# as14120_fpga_ddr_cypress.net
KiCad netlist of a schematic drawn in Altium Designer
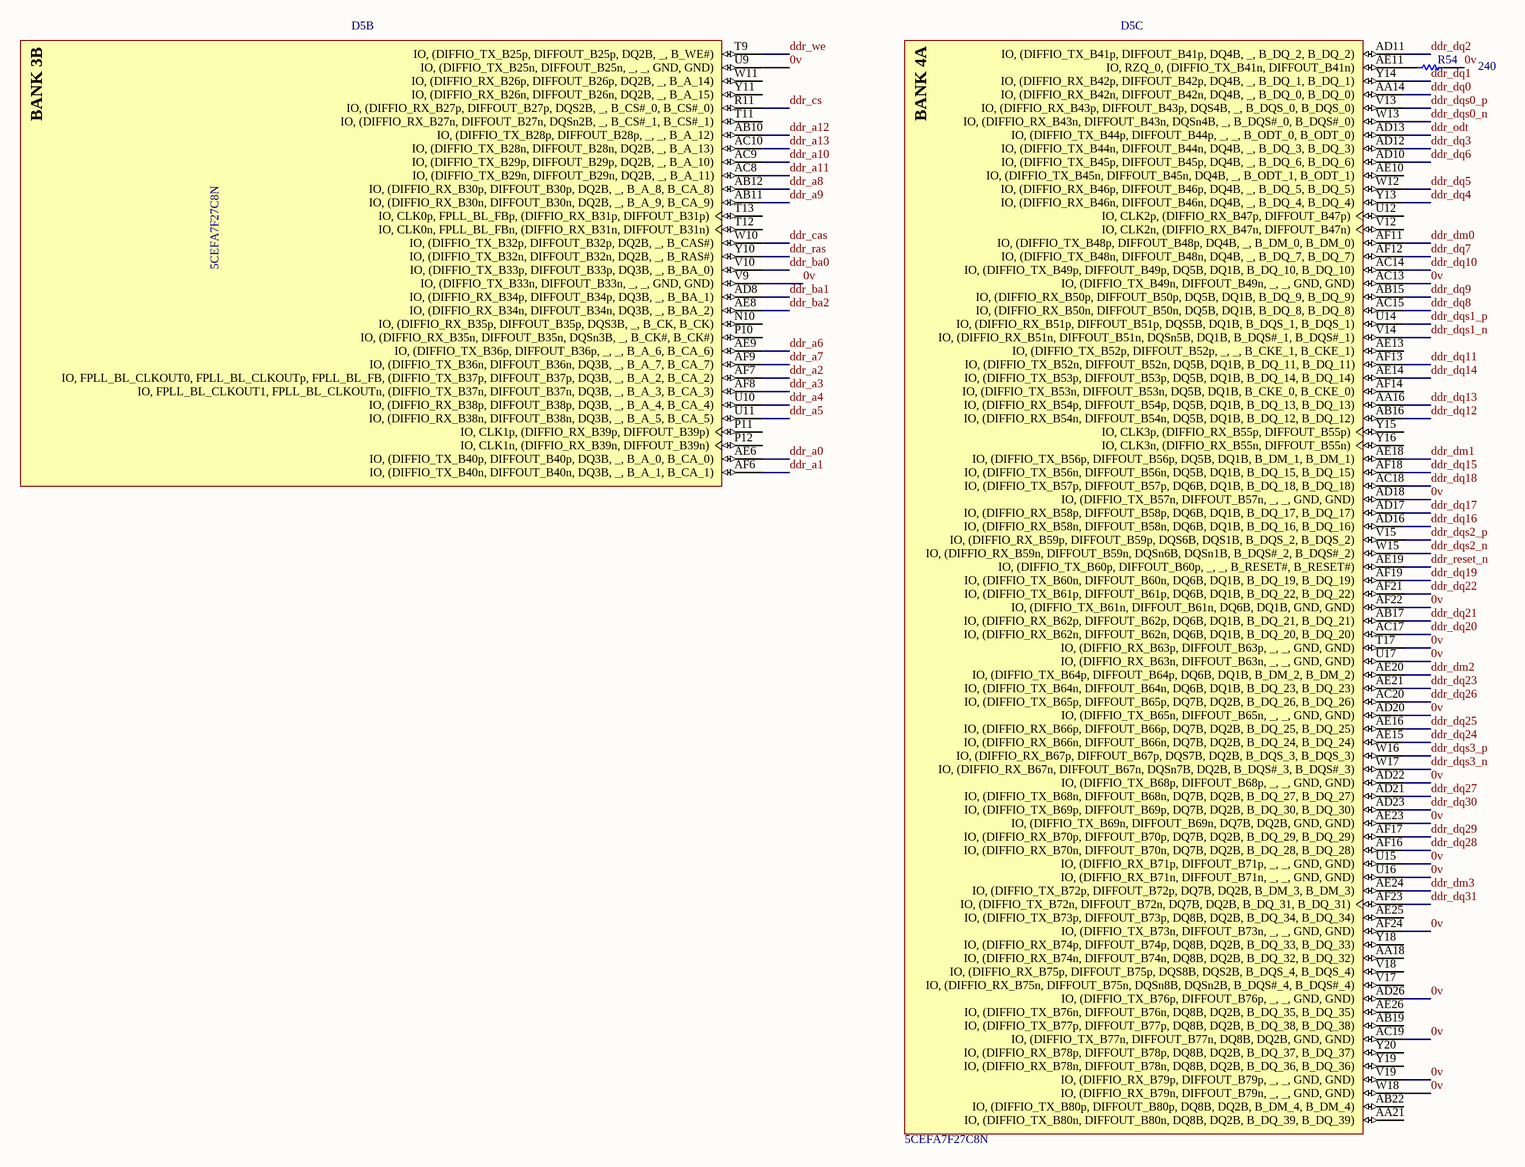
[diagram p0: as14120_fpga_ddr_cypress.SchDoc]

(export (version "E")
  (design (tool "Eeschema 10.0.6"))
  (components
    (comp (ref "D5")
      (value "5CEFA7F27C8N")
      (footprint "ALTR-672-FBGA-2000A")
      (fields (field (name "MANUFACTURER") "Altera"))
      (libsource (lib "Altera Cyclone V E") (part "5CEFA7F27C8N"))
    )
    (comp (ref "R54")
      (value "240")
      (footprint "RESC0805(2012)_L")
      (description "1K 0.125W 1% 0805 (2012 Metric)  SMD")
      (fields (field (name "TOLERANCE") "1 %") (field (name "POWER") "0.125 W"))
      (libsource (lib "as14120") (part "RES_0805"))
    )
  )
  (nets
    (net (code "1") (name "/0v") (class "Default")
      (node (ref "D5") (pin "AC13") (pinfunction "IO,_(DIFFIO_TX_B49n,_DIFFOUT_B49n,__,__,_GND,_GND)_AC13") (pintype "bidirectional"))
      (node (ref "D5") (pin "AC19") (pinfunction "IO,_(DIFFIO_TX_B77n,_DIFFOUT_B77n,_DQ8B,_DQ2B,_GND,_GND)_AC19") (pintype "bidirectional"))
      (node (ref "D5") (pin "AD18") (pinfunction "IO,_(DIFFIO_TX_B57n,_DIFFOUT_B57n,__,__,_GND,_GND)_AD18") (pintype "bidirectional"))
      (node (ref "D5") (pin "AD20") (pinfunction "IO,_(DIFFIO_TX_B65n,_DIFFOUT_B65n,__,__,_GND,_GND)_AD20") (pintype "bidirectional"))
      (node (ref "D5") (pin "AD22") (pinfunction "IO,_(DIFFIO_TX_B68p,_DIFFOUT_B68p,__,__,_GND,_GND)_AD22") (pintype "bidirectional"))
      (node (ref "D5") (pin "AD26") (pinfunction "IO,_(DIFFIO_TX_B76p,_DIFFOUT_B76p,__,__,_GND,_GND)_AD26") (pintype "bidirectional"))
      (node (ref "D5") (pin "AE23") (pinfunction "IO,_(DIFFIO_TX_B69n,_DIFFOUT_B69n,_DQ7B,_DQ2B,_GND,_GND)_AE23") (pintype "bidirectional"))
      (node (ref "D5") (pin "AF22") (pinfunction "IO,_(DIFFIO_TX_B61n,_DIFFOUT_B61n,_DQ6B,_DQ1B,_GND,_GND)_AF22") (pintype "bidirectional"))
      (node (ref "D5") (pin "AF24") (pinfunction "IO,_(DIFFIO_TX_B73n,_DIFFOUT_B73n,__,__,_GND,_GND)_AF24") (pintype "bidirectional"))
      (node (ref "D5") (pin "T17") (pinfunction "IO,_(DIFFIO_RX_B63p,_DIFFOUT_B63p,__,__,_GND,_GND)_T17") (pintype "bidirectional"))
      (node (ref "D5") (pin "U15") (pinfunction "IO,_(DIFFIO_RX_B71p,_DIFFOUT_B71p,__,__,_GND,_GND)_U15") (pintype "bidirectional"))
      (node (ref "D5") (pin "U16") (pinfunction "IO,_(DIFFIO_RX_B71n,_DIFFOUT_B71n,__,__,_GND,_GND)_U16") (pintype "bidirectional"))
      (node (ref "D5") (pin "U17") (pinfunction "IO,_(DIFFIO_RX_B63n,_DIFFOUT_B63n,__,__,_GND,_GND)_U17") (pintype "bidirectional"))
      (node (ref "D5") (pin "U9") (pinfunction "IO,_(DIFFIO_TX_B25n,_DIFFOUT_B25n,__,__,_GND,_GND)_U9") (pintype "bidirectional"))
      (node (ref "D5") (pin "V19") (pinfunction "IO,_(DIFFIO_RX_B79p,_DIFFOUT_B79p,__,__,_GND,_GND)_V19") (pintype "bidirectional"))
      (node (ref "D5") (pin "V9") (pinfunction "IO,_(DIFFIO_TX_B33n,_DIFFOUT_B33n,__,__,_GND,_GND)_V9") (pintype "bidirectional"))
      (node (ref "D5") (pin "W18") (pinfunction "IO,_(DIFFIO_RX_B79n,_DIFFOUT_B79n,__,__,_GND,_GND)_W18") (pintype "bidirectional"))
      (node (ref "R54") (pin "2") (pinfunction "2_2") (pintype "passive"))
    )
    (net (code "2") (name "/ddr_a0") (class "Default")
      (node (ref "D5") (pin "AE6") (pinfunction "IO,_(DIFFIO_TX_B40p,_DIFFOUT_B40p,_DQ3B,__,_B_A_0,_B_CA_0)_AE6") (pintype "bidirectional"))
    )
    (net (code "3") (name "/ddr_a1") (class "Default")
      (node (ref "D5") (pin "AF6") (pinfunction "IO,_(DIFFIO_TX_B40n,_DIFFOUT_B40n,_DQ3B,__,_B_A_1,_B_CA_1)_AF6") (pintype "bidirectional"))
    )
    (net (code "4") (name "/ddr_a2") (class "Default")
      (node (ref "D5") (pin "AF7") (pinfunction "IO,_FPLL_BL_CLKOUT0,_FPLL_BL_CLKOUTp,_FPLL_BL_FB,_(DIFFIO_TX_B37p,_DIFFOUT_B37p,_DQ3B,__,_B_A_2,_B_CA_2)_AF7") (pintype "bidirectional"))
    )
    (net (code "5") (name "/ddr_a3") (class "Default")
      (node (ref "D5") (pin "AF8") (pinfunction "IO,_FPLL_BL_CLKOUT1,_FPLL_BL_CLKOUTn,_(DIFFIO_TX_B37n,_DIFFOUT_B37n,_DQ3B,__,_B_A_3,_B_CA_3)_AF8") (pintype "bidirectional"))
    )
    (net (code "6") (name "/ddr_a4") (class "Default")
      (node (ref "D5") (pin "U10") (pinfunction "IO,_(DIFFIO_RX_B38p,_DIFFOUT_B38p,_DQ3B,__,_B_A_4,_B_CA_4)_U10") (pintype "bidirectional"))
    )
    (net (code "7") (name "/ddr_a5") (class "Default")
      (node (ref "D5") (pin "U11") (pinfunction "IO,_(DIFFIO_RX_B38n,_DIFFOUT_B38n,_DQ3B,__,_B_A_5,_B_CA_5)_U11") (pintype "bidirectional"))
    )
    (net (code "8") (name "/ddr_a6") (class "Default")
      (node (ref "D5") (pin "AE9") (pinfunction "IO,_(DIFFIO_TX_B36p,_DIFFOUT_B36p,__,__,_B_A_6,_B_CA_6)_AE9") (pintype "bidirectional"))
    )
    (net (code "9") (name "/ddr_a7") (class "Default")
      (node (ref "D5") (pin "AF9") (pinfunction "IO,_(DIFFIO_TX_B36n,_DIFFOUT_B36n,_DQ3B,__,_B_A_7,_B_CA_7)_AF9") (pintype "bidirectional"))
    )
    (net (code "10") (name "/ddr_a8") (class "Default")
      (node (ref "D5") (pin "AB12") (pinfunction "IO,_(DIFFIO_RX_B30p,_DIFFOUT_B30p,_DQ2B,__,_B_A_8,_B_CA_8)_AB12") (pintype "bidirectional"))
    )
    (net (code "11") (name "/ddr_a9") (class "Default")
      (node (ref "D5") (pin "AB11") (pinfunction "IO,_(DIFFIO_RX_B30n,_DIFFOUT_B30n,_DQ2B,__,_B_A_9,_B_CA_9)_AB11") (pintype "bidirectional"))
    )
    (net (code "12") (name "/ddr_a10") (class "Default")
      (node (ref "D5") (pin "AC9") (pinfunction "IO,_(DIFFIO_TX_B29p,_DIFFOUT_B29p,_DQ2B,__,_B_A_10)_AC9") (pintype "bidirectional"))
    )
    (net (code "13") (name "/ddr_a11") (class "Default")
      (node (ref "D5") (pin "AC8") (pinfunction "IO,_(DIFFIO_TX_B29n,_DIFFOUT_B29n,_DQ2B,__,_B_A_11)_AC8") (pintype "bidirectional"))
    )
    (net (code "14") (name "/ddr_a12") (class "Default")
      (node (ref "D5") (pin "AB10") (pinfunction "IO,_(DIFFIO_TX_B28p,_DIFFOUT_B28p,__,__,_B_A_12)_AB10") (pintype "bidirectional"))
    )
    (net (code "15") (name "/ddr_a13") (class "Default")
      (node (ref "D5") (pin "AC10") (pinfunction "IO,_(DIFFIO_TX_B28n,_DIFFOUT_B28n,_DQ2B,__,_B_A_13)_AC10") (pintype "bidirectional"))
    )
    (net (code "16") (name "/ddr_ba0") (class "Default")
      (node (ref "D5") (pin "V10") (pinfunction "IO,_(DIFFIO_TX_B33p,_DIFFOUT_B33p,_DQ3B,__,_B_BA_0)_V10") (pintype "bidirectional"))
    )
    (net (code "17") (name "/ddr_ba1") (class "Default")
      (node (ref "D5") (pin "AD8") (pinfunction "IO,_(DIFFIO_RX_B34p,_DIFFOUT_B34p,_DQ3B,__,_B_BA_1)_AD8") (pintype "bidirectional"))
    )
    (net (code "18") (name "/ddr_ba2") (class "Default")
      (node (ref "D5") (pin "AE8") (pinfunction "IO,_(DIFFIO_RX_B34n,_DIFFOUT_B34n,_DQ3B,__,_B_BA_2)_AE8") (pintype "bidirectional"))
    )
    (net (code "19") (name "/ddr_cas") (class "Default")
      (node (ref "D5") (pin "W10") (pinfunction "IO,_(DIFFIO_TX_B32p,_DIFFOUT_B32p,_DQ2B,__,_B_CAS#)_W10") (pintype "bidirectional"))
    )
    (net (code "20") (name "/ddr_cs") (class "Default")
      (node (ref "D5") (pin "R11") (pinfunction "IO,_(DIFFIO_RX_B27p,_DIFFOUT_B27p,_DQS2B,__,_B_CS#_0,_B_CS#_0)_R11") (pintype "bidirectional"))
    )
    (net (code "21") (name "/ddr_dm0") (class "Default")
      (node (ref "D5") (pin "AF11") (pinfunction "IO,_(DIFFIO_TX_B48p,_DIFFOUT_B48p,_DQ4B,__,_B_DM_0,_B_DM_0)_AF11") (pintype "bidirectional"))
    )
    (net (code "22") (name "/ddr_dm1") (class "Default")
      (node (ref "D5") (pin "AE18") (pinfunction "IO,_(DIFFIO_TX_B56p,_DIFFOUT_B56p,_DQ5B,_DQ1B,_B_DM_1,_B_DM_1)_AE18") (pintype "bidirectional"))
    )
    (net (code "23") (name "/ddr_dm2") (class "Default")
      (node (ref "D5") (pin "AE20") (pinfunction "IO,_(DIFFIO_TX_B64p,_DIFFOUT_B64p,_DQ6B,_DQ1B,_B_DM_2,_B_DM_2)_AE20") (pintype "bidirectional"))
    )
    (net (code "24") (name "/ddr_dm3") (class "Default")
      (node (ref "D5") (pin "AE24") (pinfunction "IO,_(DIFFIO_TX_B72p,_DIFFOUT_B72p,_DQ7B,_DQ2B,_B_DM_3,_B_DM_3)_AE24") (pintype "bidirectional"))
    )
    (net (code "25") (name "/ddr_dq0") (class "Default")
      (node (ref "D5") (pin "AA14") (pinfunction "IO,_(DIFFIO_RX_B42n,_DIFFOUT_B42n,_DQ4B,__,_B_DQ_0,_B_DQ_0)_AA14") (pintype "bidirectional"))
    )
    (net (code "26") (name "/ddr_dq1") (class "Default")
      (node (ref "D5") (pin "Y14") (pinfunction "IO,_(DIFFIO_RX_B42p,_DIFFOUT_B42p,_DQ4B,__,_B_DQ_1,_B_DQ_1)_Y14") (pintype "bidirectional"))
    )
    (net (code "27") (name "/ddr_dq2") (class "Default")
      (node (ref "D5") (pin "AD11") (pinfunction "IO,_(DIFFIO_TX_B41p,_DIFFOUT_B41p,_DQ4B,__,_B_DQ_2,_B_DQ_2)_AD11") (pintype "bidirectional"))
    )
    (net (code "28") (name "/ddr_dq3") (class "Default")
      (node (ref "D5") (pin "AD12") (pinfunction "IO,_(DIFFIO_TX_B44n,_DIFFOUT_B44n,_DQ4B,__,_B_DQ_3,_B_DQ_3)_AD12") (pintype "bidirectional"))
    )
    (net (code "29") (name "/ddr_dq4") (class "Default")
      (node (ref "D5") (pin "Y13") (pinfunction "IO,_(DIFFIO_RX_B46n,_DIFFOUT_B46n,_DQ4B,__,_B_DQ_4,_B_DQ_4)_Y13") (pintype "bidirectional"))
    )
    (net (code "30") (name "/ddr_dq5") (class "Default")
      (node (ref "D5") (pin "W12") (pinfunction "IO,_(DIFFIO_RX_B46p,_DIFFOUT_B46p,_DQ4B,__,_B_DQ_5,_B_DQ_5)_W12") (pintype "bidirectional"))
    )
    (net (code "31") (name "/ddr_dq6") (class "Default")
      (node (ref "D5") (pin "AD10") (pinfunction "IO,_(DIFFIO_TX_B45p,_DIFFOUT_B45p,_DQ4B,__,_B_DQ_6,_B_DQ_6)_AD10") (pintype "bidirectional"))
    )
    (net (code "32") (name "/ddr_dq7") (class "Default")
      (node (ref "D5") (pin "AF12") (pinfunction "IO,_(DIFFIO_TX_B48n,_DIFFOUT_B48n,_DQ4B,__,_B_DQ_7,_B_DQ_7)_AF12") (pintype "bidirectional"))
    )
    (net (code "33") (name "/ddr_dq8") (class "Default")
      (node (ref "D5") (pin "AC15") (pinfunction "IO,_(DIFFIO_RX_B50n,_DIFFOUT_B50n,_DQ5B,_DQ1B,_B_DQ_8,_B_DQ_8)_AC15") (pintype "bidirectional"))
    )
    (net (code "34") (name "/ddr_dq9") (class "Default")
      (node (ref "D5") (pin "AB15") (pinfunction "IO,_(DIFFIO_RX_B50p,_DIFFOUT_B50p,_DQ5B,_DQ1B,_B_DQ_9,_B_DQ_9)_AB15") (pintype "bidirectional"))
    )
    (net (code "35") (name "/ddr_dq10") (class "Default")
      (node (ref "D5") (pin "AC14") (pinfunction "IO,_(DIFFIO_TX_B49p,_DIFFOUT_B49p,_DQ5B,_DQ1B,_B_DQ_10,_B_DQ_10)_AC14") (pintype "bidirectional"))
    )
    (net (code "36") (name "/ddr_dq11") (class "Default")
      (node (ref "D5") (pin "AF13") (pinfunction "IO,_(DIFFIO_TX_B52n,_DIFFOUT_B52n,_DQ5B,_DQ1B,_B_DQ_11,_B_DQ_11)_AF13") (pintype "bidirectional"))
    )
    (net (code "37") (name "/ddr_dq12") (class "Default")
      (node (ref "D5") (pin "AB16") (pinfunction "IO,_(DIFFIO_RX_B54n,_DIFFOUT_B54n,_DQ5B,_DQ1B,_B_DQ_12,_B_DQ_12)_AB16") (pintype "bidirectional"))
    )
    (net (code "38") (name "/ddr_dq13") (class "Default")
      (node (ref "D5") (pin "AA16") (pinfunction "IO,_(DIFFIO_RX_B54p,_DIFFOUT_B54p,_DQ5B,_DQ1B,_B_DQ_13,_B_DQ_13)_AA16") (pintype "bidirectional"))
    )
    (net (code "39") (name "/ddr_dq14") (class "Default")
      (node (ref "D5") (pin "AE14") (pinfunction "IO,_(DIFFIO_TX_B53p,_DIFFOUT_B53p,_DQ5B,_DQ1B,_B_DQ_14,_B_DQ_14)_AE14") (pintype "bidirectional"))
    )
    (net (code "40") (name "/ddr_dq15") (class "Default")
      (node (ref "D5") (pin "AF18") (pinfunction "IO,_(DIFFIO_TX_B56n,_DIFFOUT_B56n,_DQ5B,_DQ1B,_B_DQ_15,_B_DQ_15)_AF18") (pintype "bidirectional"))
    )
    (net (code "41") (name "/ddr_dq16") (class "Default")
      (node (ref "D5") (pin "AD16") (pinfunction "IO,_(DIFFIO_RX_B58n,_DIFFOUT_B58n,_DQ6B,_DQ1B,_B_DQ_16,_B_DQ_16)_AD16") (pintype "bidirectional"))
    )
    (net (code "42") (name "/ddr_dq17") (class "Default")
      (node (ref "D5") (pin "AD17") (pinfunction "IO,_(DIFFIO_RX_B58p,_DIFFOUT_B58p,_DQ6B,_DQ1B,_B_DQ_17,_B_DQ_17)_AD17") (pintype "bidirectional"))
    )
    (net (code "43") (name "/ddr_dq18") (class "Default")
      (node (ref "D5") (pin "AC18") (pinfunction "IO,_(DIFFIO_TX_B57p,_DIFFOUT_B57p,_DQ6B,_DQ1B,_B_DQ_18,_B_DQ_18)_AC18") (pintype "bidirectional"))
    )
    (net (code "44") (name "/ddr_dq19") (class "Default")
      (node (ref "D5") (pin "AF19") (pinfunction "IO,_(DIFFIO_TX_B60n,_DIFFOUT_B60n,_DQ6B,_DQ1B,_B_DQ_19,_B_DQ_19)_AF19") (pintype "bidirectional"))
    )
    (net (code "45") (name "/ddr_dq20") (class "Default")
      (node (ref "D5") (pin "AC17") (pinfunction "IO,_(DIFFIO_RX_B62n,_DIFFOUT_B62n,_DQ6B,_DQ1B,_B_DQ_20,_B_DQ_20)_AC17") (pintype "bidirectional"))
    )
    (net (code "46") (name "/ddr_dq21") (class "Default")
      (node (ref "D5") (pin "AB17") (pinfunction "IO,_(DIFFIO_RX_B62p,_DIFFOUT_B62p,_DQ6B,_DQ1B,_B_DQ_21,_B_DQ_21)_AB17") (pintype "bidirectional"))
    )
    (net (code "47") (name "/ddr_dq22") (class "Default")
      (node (ref "D5") (pin "AF21") (pinfunction "IO,_(DIFFIO_TX_B61p,_DIFFOUT_B61p,_DQ6B,_DQ1B,_B_DQ_22,_B_DQ_22)_AF21") (pintype "bidirectional"))
    )
    (net (code "48") (name "/ddr_dq23") (class "Default")
      (node (ref "D5") (pin "AE21") (pinfunction "IO,_(DIFFIO_TX_B64n,_DIFFOUT_B64n,_DQ6B,_DQ1B,_B_DQ_23,_B_DQ_23)_AE21") (pintype "bidirectional"))
    )
    (net (code "49") (name "/ddr_dq24") (class "Default")
      (node (ref "D5") (pin "AE15") (pinfunction "IO,_(DIFFIO_RX_B66n,_DIFFOUT_B66n,_DQ7B,_DQ2B,_B_DQ_24,_B_DQ_24)_AE15") (pintype "bidirectional"))
    )
    (net (code "50") (name "/ddr_dq25") (class "Default")
      (node (ref "D5") (pin "AE16") (pinfunction "IO,_(DIFFIO_RX_B66p,_DIFFOUT_B66p,_DQ7B,_DQ2B,_B_DQ_25,_B_DQ_25)_AE16") (pintype "bidirectional"))
    )
    (net (code "51") (name "/ddr_dq26") (class "Default")
      (node (ref "D5") (pin "AC20") (pinfunction "IO,_(DIFFIO_TX_B65p,_DIFFOUT_B65p,_DQ7B,_DQ2B,_B_DQ_26,_B_DQ_26)_AC20") (pintype "bidirectional"))
    )
    (net (code "52") (name "/ddr_dq27") (class "Default")
      (node (ref "D5") (pin "AD21") (pinfunction "IO,_(DIFFIO_TX_B68n,_DIFFOUT_B68n,_DQ7B,_DQ2B,_B_DQ_27,_B_DQ_27)_AD21") (pintype "bidirectional"))
    )
    (net (code "53") (name "/ddr_dq28") (class "Default")
      (node (ref "D5") (pin "AF16") (pinfunction "IO,_(DIFFIO_RX_B70n,_DIFFOUT_B70n,_DQ7B,_DQ2B,_B_DQ_28,_B_DQ_28)_AF16") (pintype "bidirectional"))
    )
    (net (code "54") (name "/ddr_dq29") (class "Default")
      (node (ref "D5") (pin "AF17") (pinfunction "IO,_(DIFFIO_RX_B70p,_DIFFOUT_B70p,_DQ7B,_DQ2B,_B_DQ_29,_B_DQ_29)_AF17") (pintype "bidirectional"))
    )
    (net (code "55") (name "/ddr_dq30") (class "Default")
      (node (ref "D5") (pin "AD23") (pinfunction "IO,_(DIFFIO_TX_B69p,_DIFFOUT_B69p,_DQ7B,_DQ2B,_B_DQ_30,_B_DQ_30)_AD23") (pintype "bidirectional"))
    )
    (net (code "56") (name "/ddr_dq31") (class "Default")
      (node (ref "D5") (pin "AF23") (pinfunction "IO,_(DIFFIO_TX_B72n,_DIFFOUT_B72n,_DQ7B,_DQ2B,_B_DQ_31,_B_DQ_31)_AF23") (pintype "bidirectional"))
    )
    (net (code "57") (name "/ddr_dqs0_n") (class "Default")
      (node (ref "D5") (pin "W13") (pinfunction "IO,_(DIFFIO_RX_B43n,_DIFFOUT_B43n,_DQSn4B,__,_B_DQS#_0,_B_DQS#_0)_W13") (pintype "bidirectional"))
    )
    (net (code "58") (name "/ddr_dqs0_p") (class "Default")
      (node (ref "D5") (pin "V13") (pinfunction "IO,_(DIFFIO_RX_B43p,_DIFFOUT_B43p,_DQS4B,__,_B_DQS_0,_B_DQS_0)_V13") (pintype "bidirectional"))
    )
    (net (code "59") (name "/ddr_dqs1_n") (class "Default")
      (node (ref "D5") (pin "V14") (pinfunction "IO,_(DIFFIO_RX_B51n,_DIFFOUT_B51n,_DQSn5B,_DQ1B,_B_DQS#_1,_B_DQS#_1)_V14") (pintype "bidirectional"))
    )
    (net (code "60") (name "/ddr_dqs1_p") (class "Default")
      (node (ref "D5") (pin "U14") (pinfunction "IO,_(DIFFIO_RX_B51p,_DIFFOUT_B51p,_DQS5B,_DQ1B,_B_DQS_1,_B_DQS_1)_U14") (pintype "bidirectional"))
    )
    (net (code "61") (name "/ddr_dqs2_n") (class "Default")
      (node (ref "D5") (pin "W15") (pinfunction "IO,_(DIFFIO_RX_B59n,_DIFFOUT_B59n,_DQSn6B,_DQSn1B,_B_DQS#_2,_B_DQS#_2)_W15") (pintype "bidirectional"))
    )
    (net (code "62") (name "/ddr_dqs2_p") (class "Default")
      (node (ref "D5") (pin "V15") (pinfunction "IO,_(DIFFIO_RX_B59p,_DIFFOUT_B59p,_DQS6B,_DQS1B,_B_DQS_2,_B_DQS_2)_V15") (pintype "bidirectional"))
    )
    (net (code "63") (name "/ddr_dqs3_n") (class "Default")
      (node (ref "D5") (pin "W17") (pinfunction "IO,_(DIFFIO_RX_B67n,_DIFFOUT_B67n,_DQSn7B,_DQ2B,_B_DQS#_3,_B_DQS#_3)_W17") (pintype "bidirectional"))
    )
    (net (code "64") (name "/ddr_dqs3_p") (class "Default")
      (node (ref "D5") (pin "W16") (pinfunction "IO,_(DIFFIO_RX_B67p,_DIFFOUT_B67p,_DQS7B,_DQ2B,_B_DQS_3,_B_DQS_3)_W16") (pintype "bidirectional"))
    )
    (net (code "65") (name "/ddr_odt") (class "Default")
      (node (ref "D5") (pin "AD13") (pinfunction "IO,_(DIFFIO_TX_B44p,_DIFFOUT_B44p,__,__,_B_ODT_0,_B_ODT_0)_AD13") (pintype "bidirectional"))
    )
    (net (code "66") (name "/ddr_ras") (class "Default")
      (node (ref "D5") (pin "Y10") (pinfunction "IO,_(DIFFIO_TX_B32n,_DIFFOUT_B32n,_DQ2B,__,_B_RAS#)_Y10") (pintype "bidirectional"))
    )
    (net (code "67") (name "/ddr_reset_n") (class "Default")
      (node (ref "D5") (pin "AE19") (pinfunction "IO,_(DIFFIO_TX_B60p,_DIFFOUT_B60p,__,__,_B_RESET#,_B_RESET#)_AE19") (pintype "bidirectional"))
    )
    (net (code "68") (name "/ddr_we") (class "Default")
      (node (ref "D5") (pin "T9") (pinfunction "IO,_(DIFFIO_TX_B25p,_DIFFOUT_B25p,_DQ2B,__,_B_WE#)_T9") (pintype "bidirectional"))
    )
    (net (code "69") (name "Net-(D5C-IO,_RZQ_0,_(DIFFIO_TX_B41n,_DIFFOUT_B41n))") (class "Default")
      (node (ref "D5") (pin "AE11") (pinfunction "IO,_RZQ_0,_(DIFFIO_TX_B41n,_DIFFOUT_B41n)_AE11") (pintype "bidirectional"))
      (node (ref "R54") (pin "1") (pinfunction "1_1") (pintype "passive"))
    )
    (net (code "70") (name "unconnected-(D5B-IO,_(DIFFIO_RX_B26n,_DIFFOUT_B26n,_DQ2B,__,_B_A_15)-PadY11)") (class "Default")
      (node (ref "D5") (pin "Y11") (pinfunction "IO,_(DIFFIO_RX_B26n,_DIFFOUT_B26n,_DQ2B,__,_B_A_15)_Y11") (pintype "bidirectional"))
    )
    (net (code "71") (name "unconnected-(D5B-IO,_(DIFFIO_RX_B26p,_DIFFOUT_B26p,_DQ2B,__,_B_A_14)-PadW11)") (class "Default")
      (node (ref "D5") (pin "W11") (pinfunction "IO,_(DIFFIO_RX_B26p,_DIFFOUT_B26p,_DQ2B,__,_B_A_14)_W11") (pintype "bidirectional"))
    )
    (net (code "72") (name "unconnected-(D5B-IO,_(DIFFIO_RX_B27n,_DIFFOUT_B27n,_DQSn2B,__,_B_CS#_1,_B_CS#_1)-PadT11)") (class "Default")
      (node (ref "D5") (pin "T11") (pinfunction "IO,_(DIFFIO_RX_B27n,_DIFFOUT_B27n,_DQSn2B,__,_B_CS#_1,_B_CS#_1)_T11") (pintype "bidirectional"))
    )
    (net (code "73") (name "unconnected-(D5B-IO,_(DIFFIO_RX_B35n,_DIFFOUT_B35n,_DQSn3B,__,_B_CK#,_B_CK#)-PadP10)") (class "Default")
      (node (ref "D5") (pin "P10") (pinfunction "IO,_(DIFFIO_RX_B35n,_DIFFOUT_B35n,_DQSn3B,__,_B_CK#,_B_CK#)_P10") (pintype "bidirectional"))
    )
    (net (code "74") (name "unconnected-(D5B-IO,_(DIFFIO_RX_B35p,_DIFFOUT_B35p,_DQS3B,__,_B_CK,_B_CK)-PadN10)") (class "Default")
      (node (ref "D5") (pin "N10") (pinfunction "IO,_(DIFFIO_RX_B35p,_DIFFOUT_B35p,_DQS3B,__,_B_CK,_B_CK)_N10") (pintype "bidirectional"))
    )
    (net (code "75") (name "unconnected-(D5B-IO,_CLK0n,_FPLL_BL_FBn,_(DIFFIO_RX_B31n,_DIFFOUT_B31n)-PadT12)") (class "Default")
      (node (ref "D5") (pin "T12") (pinfunction "IO,_CLK0n,_FPLL_BL_FBn,_(DIFFIO_RX_B31n,_DIFFOUT_B31n)_T12") (pintype "bidirectional"))
    )
    (net (code "76") (name "unconnected-(D5B-IO,_CLK0p,_FPLL_BL_FBp,_(DIFFIO_RX_B31p,_DIFFOUT_B31p)-PadT13)") (class "Default")
      (node (ref "D5") (pin "T13") (pinfunction "IO,_CLK0p,_FPLL_BL_FBp,_(DIFFIO_RX_B31p,_DIFFOUT_B31p)_T13") (pintype "bidirectional"))
    )
    (net (code "77") (name "unconnected-(D5B-IO,_CLK1n,_(DIFFIO_RX_B39n,_DIFFOUT_B39n)-PadP12)") (class "Default")
      (node (ref "D5") (pin "P12") (pinfunction "IO,_CLK1n,_(DIFFIO_RX_B39n,_DIFFOUT_B39n)_P12") (pintype "bidirectional"))
    )
    (net (code "78") (name "unconnected-(D5B-IO,_CLK1p,_(DIFFIO_RX_B39p,_DIFFOUT_B39p)-PadP11)") (class "Default")
      (node (ref "D5") (pin "P11") (pinfunction "IO,_CLK1p,_(DIFFIO_RX_B39p,_DIFFOUT_B39p)_P11") (pintype "bidirectional"))
    )
    (net (code "79") (name "unconnected-(D5C-IO,_(DIFFIO_RX_B74n,_DIFFOUT_B74n,_DQ8B,_DQ2B,_B_DQ_32,_B_DQ_32)-PadAA18)") (class "Default")
      (node (ref "D5") (pin "AA18") (pinfunction "IO,_(DIFFIO_RX_B74n,_DIFFOUT_B74n,_DQ8B,_DQ2B,_B_DQ_32,_B_DQ_32)_AA18") (pintype "bidirectional"))
    )
    (net (code "80") (name "unconnected-(D5C-IO,_(DIFFIO_RX_B74p,_DIFFOUT_B74p,_DQ8B,_DQ2B,_B_DQ_33,_B_DQ_33)-PadY18)") (class "Default")
      (node (ref "D5") (pin "Y18") (pinfunction "IO,_(DIFFIO_RX_B74p,_DIFFOUT_B74p,_DQ8B,_DQ2B,_B_DQ_33,_B_DQ_33)_Y18") (pintype "bidirectional"))
    )
    (net (code "81") (name "unconnected-(D5C-IO,_(DIFFIO_RX_B75n,_DIFFOUT_B75n,_DQSn8B,_DQSn2B,_B_DQS#_4,_B_DQS#_4)-PadV17)") (class "Default")
      (node (ref "D5") (pin "V17") (pinfunction "IO,_(DIFFIO_RX_B75n,_DIFFOUT_B75n,_DQSn8B,_DQSn2B,_B_DQS#_4,_B_DQS#_4)_V17") (pintype "bidirectional"))
    )
    (net (code "82") (name "unconnected-(D5C-IO,_(DIFFIO_RX_B75p,_DIFFOUT_B75p,_DQS8B,_DQS2B,_B_DQS_4,_B_DQS_4)-PadV18)") (class "Default")
      (node (ref "D5") (pin "V18") (pinfunction "IO,_(DIFFIO_RX_B75p,_DIFFOUT_B75p,_DQS8B,_DQS2B,_B_DQS_4,_B_DQS_4)_V18") (pintype "bidirectional"))
    )
    (net (code "83") (name "unconnected-(D5C-IO,_(DIFFIO_RX_B78n,_DIFFOUT_B78n,_DQ8B,_DQ2B,_B_DQ_36,_B_DQ_36)-PadY19)") (class "Default")
      (node (ref "D5") (pin "Y19") (pinfunction "IO,_(DIFFIO_RX_B78n,_DIFFOUT_B78n,_DQ8B,_DQ2B,_B_DQ_36,_B_DQ_36)_Y19") (pintype "bidirectional"))
    )
    (net (code "84") (name "unconnected-(D5C-IO,_(DIFFIO_RX_B78p,_DIFFOUT_B78p,_DQ8B,_DQ2B,_B_DQ_37,_B_DQ_37)-PadY20)") (class "Default")
      (node (ref "D5") (pin "Y20") (pinfunction "IO,_(DIFFIO_RX_B78p,_DIFFOUT_B78p,_DQ8B,_DQ2B,_B_DQ_37,_B_DQ_37)_Y20") (pintype "bidirectional"))
    )
    (net (code "85") (name "unconnected-(D5C-IO,_(DIFFIO_TX_B45n,_DIFFOUT_B45n,_DQ4B,__,_B_ODT_1,_B_ODT_1)-PadAE10)") (class "Default")
      (node (ref "D5") (pin "AE10") (pinfunction "IO,_(DIFFIO_TX_B45n,_DIFFOUT_B45n,_DQ4B,__,_B_ODT_1,_B_ODT_1)_AE10") (pintype "bidirectional"))
    )
    (net (code "86") (name "unconnected-(D5C-IO,_(DIFFIO_TX_B52p,_DIFFOUT_B52p,__,__,_B_CKE_1,_B_CKE_1)-PadAE13)") (class "Default")
      (node (ref "D5") (pin "AE13") (pinfunction "IO,_(DIFFIO_TX_B52p,_DIFFOUT_B52p,__,__,_B_CKE_1,_B_CKE_1)_AE13") (pintype "bidirectional"))
    )
    (net (code "87") (name "unconnected-(D5C-IO,_(DIFFIO_TX_B53n,_DIFFOUT_B53n,_DQ5B,_DQ1B,_B_CKE_0,_B_CKE_0)-PadAF14)") (class "Default")
      (node (ref "D5") (pin "AF14") (pinfunction "IO,_(DIFFIO_TX_B53n,_DIFFOUT_B53n,_DQ5B,_DQ1B,_B_CKE_0,_B_CKE_0)_AF14") (pintype "bidirectional"))
    )
    (net (code "88") (name "unconnected-(D5C-IO,_(DIFFIO_TX_B73p,_DIFFOUT_B73p,_DQ8B,_DQ2B,_B_DQ_34,_B_DQ_34)-PadAE25)") (class "Default")
      (node (ref "D5") (pin "AE25") (pinfunction "IO,_(DIFFIO_TX_B73p,_DIFFOUT_B73p,_DQ8B,_DQ2B,_B_DQ_34,_B_DQ_34)_AE25") (pintype "bidirectional"))
    )
    (net (code "89") (name "unconnected-(D5C-IO,_(DIFFIO_TX_B76n,_DIFFOUT_B76n,_DQ8B,_DQ2B,_B_DQ_35,_B_DQ_35)-PadAE26)") (class "Default")
      (node (ref "D5") (pin "AE26") (pinfunction "IO,_(DIFFIO_TX_B76n,_DIFFOUT_B76n,_DQ8B,_DQ2B,_B_DQ_35,_B_DQ_35)_AE26") (pintype "bidirectional"))
    )
    (net (code "90") (name "unconnected-(D5C-IO,_(DIFFIO_TX_B77p,_DIFFOUT_B77p,_DQ8B,_DQ2B,_B_DQ_38,_B_DQ_38)-PadAB19)") (class "Default")
      (node (ref "D5") (pin "AB19") (pinfunction "IO,_(DIFFIO_TX_B77p,_DIFFOUT_B77p,_DQ8B,_DQ2B,_B_DQ_38,_B_DQ_38)_AB19") (pintype "bidirectional"))
    )
    (net (code "91") (name "unconnected-(D5C-IO,_(DIFFIO_TX_B80n,_DIFFOUT_B80n,_DQ8B,_DQ2B,_B_DQ_39,_B_DQ_39)-PadAA21)") (class "Default")
      (node (ref "D5") (pin "AA21") (pinfunction "IO,_(DIFFIO_TX_B80n,_DIFFOUT_B80n,_DQ8B,_DQ2B,_B_DQ_39,_B_DQ_39)_AA21") (pintype "bidirectional"))
    )
    (net (code "92") (name "unconnected-(D5C-IO,_(DIFFIO_TX_B80p,_DIFFOUT_B80p,_DQ8B,_DQ2B,_B_DM_4,_B_DM_4)-PadAB22)") (class "Default")
      (node (ref "D5") (pin "AB22") (pinfunction "IO,_(DIFFIO_TX_B80p,_DIFFOUT_B80p,_DQ8B,_DQ2B,_B_DM_4,_B_DM_4)_AB22") (pintype "bidirectional"))
    )
    (net (code "93") (name "unconnected-(D5C-IO,_CLK2n,_(DIFFIO_RX_B47n,_DIFFOUT_B47n)-PadV12)") (class "Default")
      (node (ref "D5") (pin "V12") (pinfunction "IO,_CLK2n,_(DIFFIO_RX_B47n,_DIFFOUT_B47n)_V12") (pintype "bidirectional"))
    )
    (net (code "94") (name "unconnected-(D5C-IO,_CLK2p,_(DIFFIO_RX_B47p,_DIFFOUT_B47p)-PadU12)") (class "Default")
      (node (ref "D5") (pin "U12") (pinfunction "IO,_CLK2p,_(DIFFIO_RX_B47p,_DIFFOUT_B47p)_U12") (pintype "bidirectional"))
    )
    (net (code "95") (name "unconnected-(D5C-IO,_CLK3n,_(DIFFIO_RX_B55n,_DIFFOUT_B55n)-PadY16)") (class "Default")
      (node (ref "D5") (pin "Y16") (pinfunction "IO,_CLK3n,_(DIFFIO_RX_B55n,_DIFFOUT_B55n)_Y16") (pintype "bidirectional"))
    )
    (net (code "96") (name "unconnected-(D5C-IO,_CLK3p,_(DIFFIO_RX_B55p,_DIFFOUT_B55p)-PadY15)") (class "Default")
      (node (ref "D5") (pin "Y15") (pinfunction "IO,_CLK3p,_(DIFFIO_RX_B55p,_DIFFOUT_B55p)_Y15") (pintype "bidirectional"))
    )
  )
)
